# LightSensorSchematic.net
KiCad netlist of a schematic drawn in Altium Designer
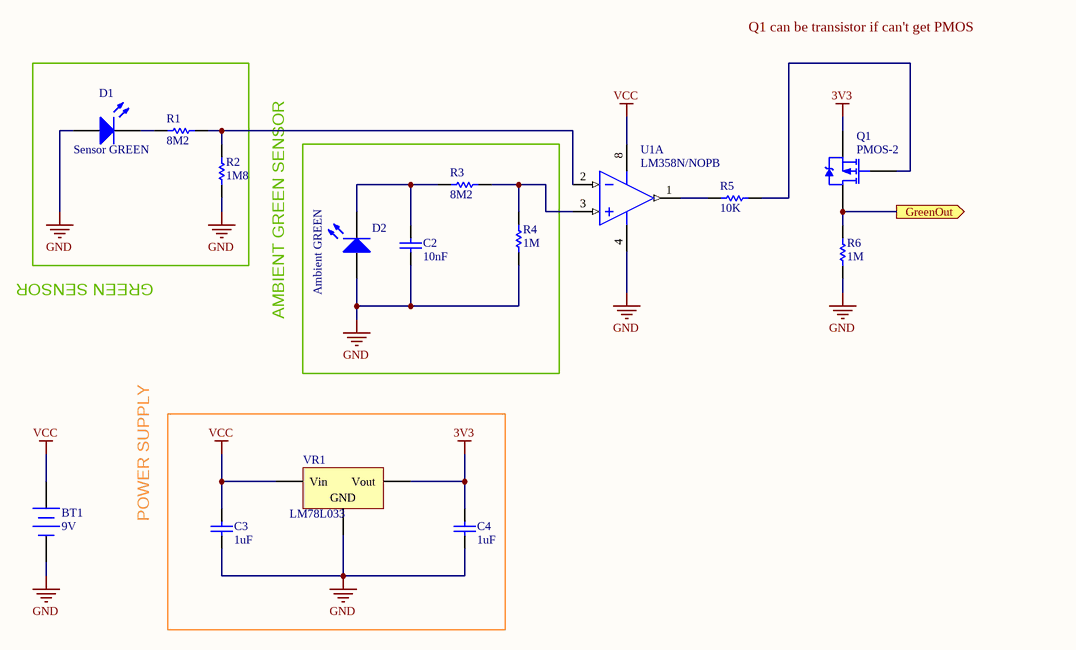
[diagram p0: LightSensorSchematic.SchDoc]

(export (version "E")
  (design (tool "Eeschema 10.0.6"))
  (components
    (comp (ref "BT1")
      (value "9V")
      (footprint "BAT-2")
      (description "Multicell Battery")
      (fields (field (name "PUBLISHER") "Altium Limited"))
      (libsource (lib "Miscellaneous Devices") (part "Battery"))
    )
    (comp (ref "C2")
      (value "10nF")
      (footprint "RAD-0.3")
      (description "Capacitor")
      (fields (field (name "PUBLISHER") "Altium Limited"))
      (libsource (lib "Miscellaneous Devices") (part "Cap"))
    )
    (comp (ref "C3")
      (value "1uF")
      (footprint "RAD-0.3")
      (description "Capacitor")
      (fields (field (name "PUBLISHER") "Altium Limited"))
      (libsource (lib "Miscellaneous Devices") (part "Cap"))
    )
    (comp (ref "C4")
      (value "1uF")
      (footprint "RAD-0.3")
      (description "Capacitor")
      (fields (field (name "PUBLISHER") "Altium Limited"))
      (libsource (lib "Miscellaneous Devices") (part "Cap"))
    )
    (comp (ref "D1")
      (value "Sensor GREEN")
      (footprint "LED-0")
      (description "Typical INFRARED GaAs LED")
      (fields (field (name "PUBLISHER") "Altium Limited"))
      (libsource (lib "Miscellaneous Devices") (part "LED0"))
    )
    (comp (ref "D2")
      (value "Ambient GREEN")
      (footprint "LED-0")
      (description "Typical INFRARED GaAs LED")
      (fields (field (name "PUBLISHER") "Altium Limited"))
      (libsource (lib "Miscellaneous Devices") (part "LED0"))
    )
    (comp (ref "Q1")
      (value "PMOS-2")
      (footprint "TO-220AB")
      (description "P-Channel Power MOSFET")
      (fields (field (name "PUBLISHER") "Altium Limited"))
      (libsource (lib "Miscellaneous Devices") (part "PMOS-2"))
    )
    (comp (ref "R1")
      (value "8M2")
      (footprint "AXIAL-0.3")
      (description "Resistor")
      (fields (field (name "PUBLISHER") "Altium Limited"))
      (libsource (lib "Miscellaneous Devices") (part "Res1"))
    )
    (comp (ref "R2")
      (value "1M8")
      (footprint "AXIAL-0.3")
      (description "Resistor")
      (fields (field (name "PUBLISHER") "Altium Limited"))
      (libsource (lib "Miscellaneous Devices") (part "Res1"))
    )
    (comp (ref "R3")
      (value "8M2")
      (footprint "AXIAL-0.3")
      (description "Resistor")
      (fields (field (name "PUBLISHER") "Altium Limited"))
      (libsource (lib "Miscellaneous Devices") (part "Res1"))
    )
    (comp (ref "R4")
      (value "1M")
      (footprint "AXIAL-0.3")
      (description "Resistor")
      (fields (field (name "PUBLISHER") "Altium Limited"))
      (libsource (lib "Miscellaneous Devices") (part "Res1"))
    )
    (comp (ref "R5")
      (value "10K")
      (footprint "AXIAL-0.3")
      (description "Resistor")
      (fields (field (name "PUBLISHER") "Altium Limited"))
      (libsource (lib "Miscellaneous Devices") (part "Res1"))
    )
    (comp (ref "R6")
      (value "1M")
      (footprint "AXIAL-0.3")
      (description "Resistor")
      (fields (field (name "PUBLISHER") "Altium Limited"))
      (libsource (lib "Miscellaneous Devices") (part "Res1"))
    )
    (comp (ref "U1")
      (value "LM358N/NOPB")
      (footprint "N08E")
      (description "Low Power Dual Operational Amplifier, 8-pin MDIP, Pb-Free")
      (fields (field (name "MANUFACTURER") "National Semiconductor"))
      (libsource (lib "Altium Content Vault") (part "AMP-OPA-LM158-8"))
    )
    (comp (ref "VR1")
      (value "LM78L033")
      (footprint "D2PAK_N")
      (description "Voltage Regulator")
      (fields (field (name "PUBLISHER") "Altium Limited"))
      (libsource (lib "Miscellaneous Devices") (part "Volt Reg"))
    )
  )
  (nets
    (net (code "1") (name "/GreenOut") (class "Default")
      (node (ref "Q1") (pin "2") (pinfunction "D_2") (pintype "passive"))
      (node (ref "R6") (pin "2") (pinfunction "2_2") (pintype "passive"))
    )
    (net (code "2") (name "3V3") (class "Default")
      (node (ref "C4") (pin "2") (pinfunction "2_2") (pintype "passive"))
      (node (ref "Q1") (pin "3") (pinfunction "S_3") (pintype "passive"))
      (node (ref "VR1") (pin "3") (pinfunction "Vout_3") (pintype "passive"))
    )
    (net (code "3") (name "GND") (class "Default")
      (node (ref "BT1") (pin "2") (pinfunction "-_2") (pintype "passive"))
      (node (ref "C2") (pin "1") (pinfunction "1_1") (pintype "passive"))
      (node (ref "C3") (pin "1") (pinfunction "1_1") (pintype "passive"))
      (node (ref "C4") (pin "1") (pinfunction "1_1") (pintype "passive"))
      (node (ref "D1") (pin "1") (pinfunction "A_1") (pintype "passive"))
      (node (ref "D2") (pin "1") (pinfunction "A_1") (pintype "passive"))
      (node (ref "R2") (pin "1") (pinfunction "1_1") (pintype "passive"))
      (node (ref "R4") (pin "1") (pinfunction "1_1") (pintype "passive"))
      (node (ref "R6") (pin "1") (pinfunction "1_1") (pintype "passive"))
      (node (ref "U1") (pin "4") (pinfunction "GND_4") (pintype "power_in"))
      (node (ref "VR1") (pin "2") (pinfunction "GND_2") (pintype "passive"))
    )
    (net (code "4") (name "Net-(D1-K)") (class "Default")
      (node (ref "D1") (pin "2") (pinfunction "K_2") (pintype "passive"))
      (node (ref "R1") (pin "1") (pinfunction "1_1") (pintype "passive"))
    )
    (net (code "5") (name "Net-(D2-K)") (class "Default")
      (node (ref "C2") (pin "2") (pinfunction "2_2") (pintype "passive"))
      (node (ref "D2") (pin "2") (pinfunction "K_2") (pintype "passive"))
      (node (ref "R3") (pin "1") (pinfunction "1_1") (pintype "passive"))
    )
    (net (code "6") (name "Net-(Q1-G)") (class "Default")
      (node (ref "Q1") (pin "1") (pinfunction "G_1") (pintype "passive"))
      (node (ref "R5") (pin "2") (pinfunction "2_2") (pintype "passive"))
    )
    (net (code "7") (name "Net-(U1A-INA+)") (class "Default")
      (node (ref "R3") (pin "2") (pinfunction "2_2") (pintype "passive"))
      (node (ref "R4") (pin "2") (pinfunction "2_2") (pintype "passive"))
      (node (ref "U1") (pin "3") (pinfunction "INA+_3") (pintype "input"))
    )
    (net (code "8") (name "Net-(U1A-INA-)") (class "Default")
      (node (ref "R1") (pin "2") (pinfunction "2_2") (pintype "passive"))
      (node (ref "R2") (pin "2") (pinfunction "2_2") (pintype "passive"))
      (node (ref "U1") (pin "2") (pinfunction "INA-_2") (pintype "input"))
    )
    (net (code "9") (name "Net-(U1A-OUTA)") (class "Default")
      (node (ref "R5") (pin "1") (pinfunction "1_1") (pintype "passive"))
      (node (ref "U1") (pin "1") (pinfunction "OUTA_1") (pintype "output"))
    )
    (net (code "10") (name "VCC") (class "Default")
      (node (ref "BT1") (pin "1") (pinfunction "+_1") (pintype "passive"))
      (node (ref "C3") (pin "2") (pinfunction "2_2") (pintype "passive"))
      (node (ref "U1") (pin "8") (pinfunction "V+_8") (pintype "power_in"))
      (node (ref "VR1") (pin "1") (pinfunction "Vin_1") (pintype "passive"))
    )
  )
)
